# releBoard_v10.net
KiCad netlist of a schematic drawn in EAGLE
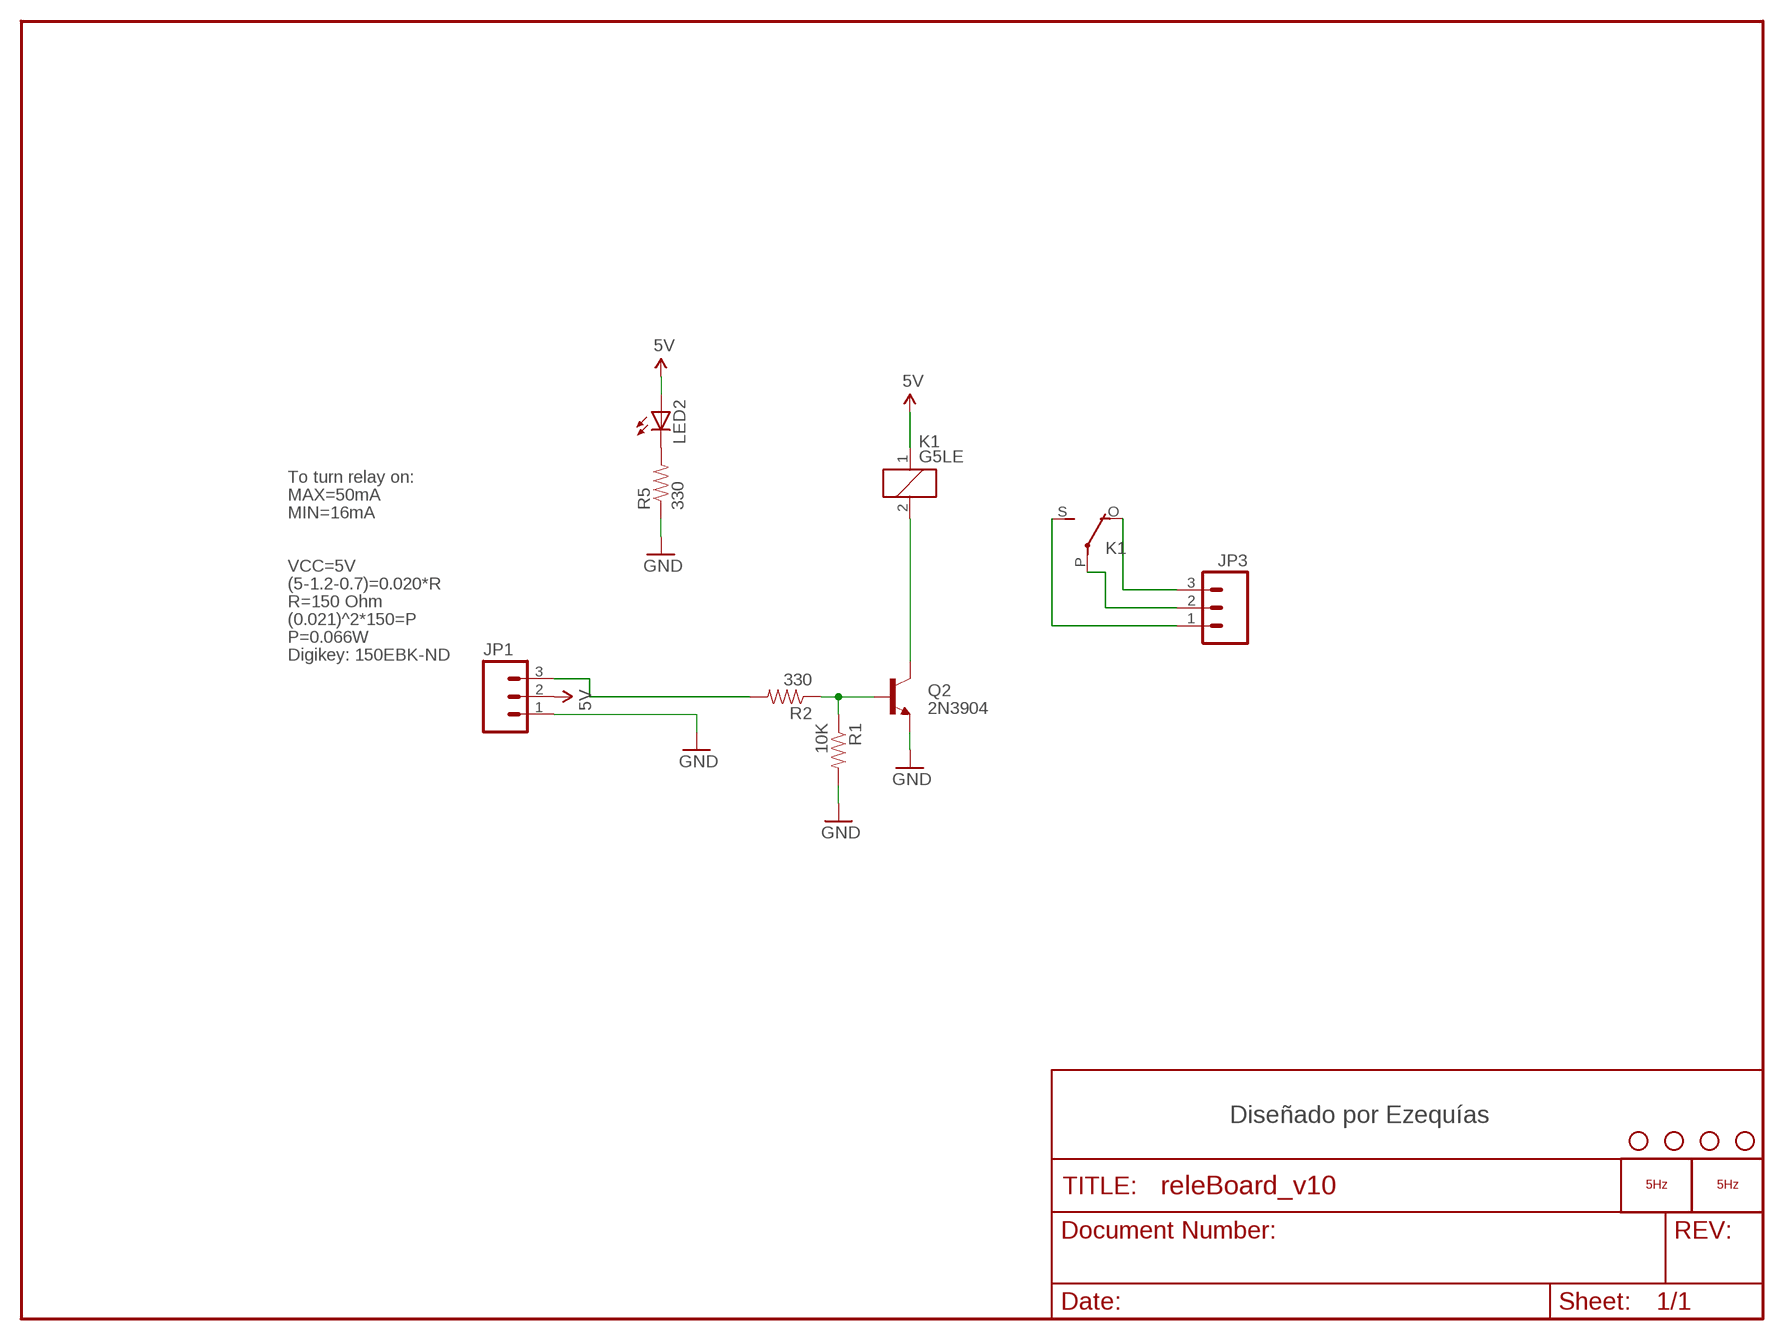
[diagram p0: schematic, sheet 1]

(export (version "E")
  (design (tool "Eeschema 10.0.6"))
  (components
    (comp (ref "JP1")
      (value "M03POLAR")
      (footprint "eagle-import:MOLEX-1X3")
      (libsource (lib "eagle-import") (part "M03POLAR"))
    )
    (comp (ref "JP3")
      (value "M03-SCREW-5MM")
      (footprint "eagle-import:SCREWTERMINAL-5MM-3")
      (libsource (lib "eagle-import") (part "M03-SCREW-5MM"))
    )
    (comp (ref "K1")
      (value "G5LE")
      (footprint "eagle-import:G5LE")
      (libsource (lib "eagle-import") (part "G5LE"))
    )
    (comp (ref "LED2")
      (value "LED0603")
      (footprint "eagle-import:LED-0603")
      (libsource (lib "eagle-import") (part "LED0603"))
    )
    (comp (ref "LOGO1")
      (value "LOGO_5HZ_H_15MM")
      (footprint "eagle-import:5HZ_LOGO_H_15MM")
      (libsource (lib "eagle-import") (part "LOGO_5HZ_H_15MM"))
    )
    (comp (ref "LOGO2")
      (value "LOGO_5HZ_WEB_COOPER_10MM")
      (footprint "eagle-import:5HZ_WEB_COOPER_10MM")
      (libsource (lib "eagle-import") (part "LOGO_5HZ_WEB_COOPER_10MM"))
    )
    (comp (ref "Q2")
      (value "2N3904")
      (footprint "eagle-import:SOT23")
      (libsource (lib "eagle-import") (part "TRANSISTOR_NPNSOT23"))
    )
    (comp (ref "R1")
      (value "10K")
      (footprint "eagle-import:0603-RES")
      (libsource (lib "eagle-import") (part "RESISTOR0603-RES"))
    )
    (comp (ref "R2")
      (value "330")
      (footprint "eagle-import:0603-RES")
      (libsource (lib "eagle-import") (part "RESISTOR0603-RES"))
    )
    (comp (ref "R5")
      (value "330")
      (footprint "eagle-import:0603-RES")
      (libsource (lib "eagle-import") (part "RESISTOR0603-RES"))
    )
    (comp (ref "U$3")
      (value "STAND-OFF")
      (footprint "eagle-import:STAND-OFF")
      (libsource (lib "eagle-import") (part "STAND-OFF"))
    )
    (comp (ref "U$4")
      (value "STAND-OFF")
      (footprint "eagle-import:STAND-OFF")
      (libsource (lib "eagle-import") (part "STAND-OFF"))
    )
    (comp (ref "U$5")
      (value "STAND-OFF")
      (footprint "eagle-import:STAND-OFF")
      (libsource (lib "eagle-import") (part "STAND-OFF"))
    )
    (comp (ref "U$7")
      (value "STAND-OFF")
      (footprint "eagle-import:STAND-OFF")
      (libsource (lib "eagle-import") (part "STAND-OFF"))
    )
  )
  (nets
    (net (code "1") (name "5V") (class "Default")
      (node (ref "JP1") (pin "2") (pinfunction "2_2") (pintype "passive"))
      (node (ref "K1") (pin "1") (pinfunction "1_1") (pintype "passive"))
      (node (ref "LED2") (pin "A") (pinfunction "A_A") (pintype "passive"))
    )
    (net (code "2") (name "GND") (class "Default")
      (node (ref "JP1") (pin "1") (pinfunction "1_1") (pintype "passive"))
      (node (ref "Q2") (pin "2") (pinfunction "E_2") (pintype "passive"))
      (node (ref "R1") (pin "2") (pinfunction "2_2") (pintype "passive"))
      (node (ref "R5") (pin "1") (pinfunction "1_1") (pintype "passive"))
    )
    (net (code "3") (name "Net-(JP1-Pad3)") (class "Default")
      (node (ref "JP1") (pin "3") (pinfunction "3_3") (pintype "passive"))
      (node (ref "R2") (pin "2") (pinfunction "2_2") (pintype "passive"))
    )
    (net (code "4") (name "Net-(JP3-Pad1)") (class "Default")
      (node (ref "JP3") (pin "1") (pinfunction "1_1") (pintype "passive"))
      (node (ref "K1") (pin "S") (pinfunction "S_S") (pintype "passive"))
    )
    (net (code "5") (name "Net-(JP3-Pad2)") (class "Default")
      (node (ref "JP3") (pin "2") (pinfunction "2_2") (pintype "passive"))
      (node (ref "K1") (pin "P") (pinfunction "P_P") (pintype "passive"))
    )
    (net (code "6") (name "Net-(JP3-Pad3)") (class "Default")
      (node (ref "JP3") (pin "3") (pinfunction "3_3") (pintype "passive"))
      (node (ref "K1") (pin "O") (pinfunction "O_O") (pintype "passive"))
    )
    (net (code "7") (name "Net-(LED2-PadC)") (class "Default")
      (node (ref "LED2") (pin "C") (pinfunction "C_C") (pintype "passive"))
      (node (ref "R5") (pin "2") (pinfunction "2_2") (pintype "passive"))
    )
    (net (code "8") (name "Net-(Q2-B)") (class "Default")
      (node (ref "Q2") (pin "1") (pinfunction "B_1") (pintype "passive"))
      (node (ref "R1") (pin "1") (pinfunction "1_1") (pintype "passive"))
      (node (ref "R2") (pin "1") (pinfunction "1_1") (pintype "passive"))
    )
    (net (code "9") (name "Net-(Q2-C)") (class "Default")
      (node (ref "K1") (pin "2") (pinfunction "2_2") (pintype "passive"))
      (node (ref "Q2") (pin "3") (pinfunction "C_3") (pintype "passive"))
    )
  )
)
